# sheet1.net
KiCad netlist of a schematic drawn in Altium Designer
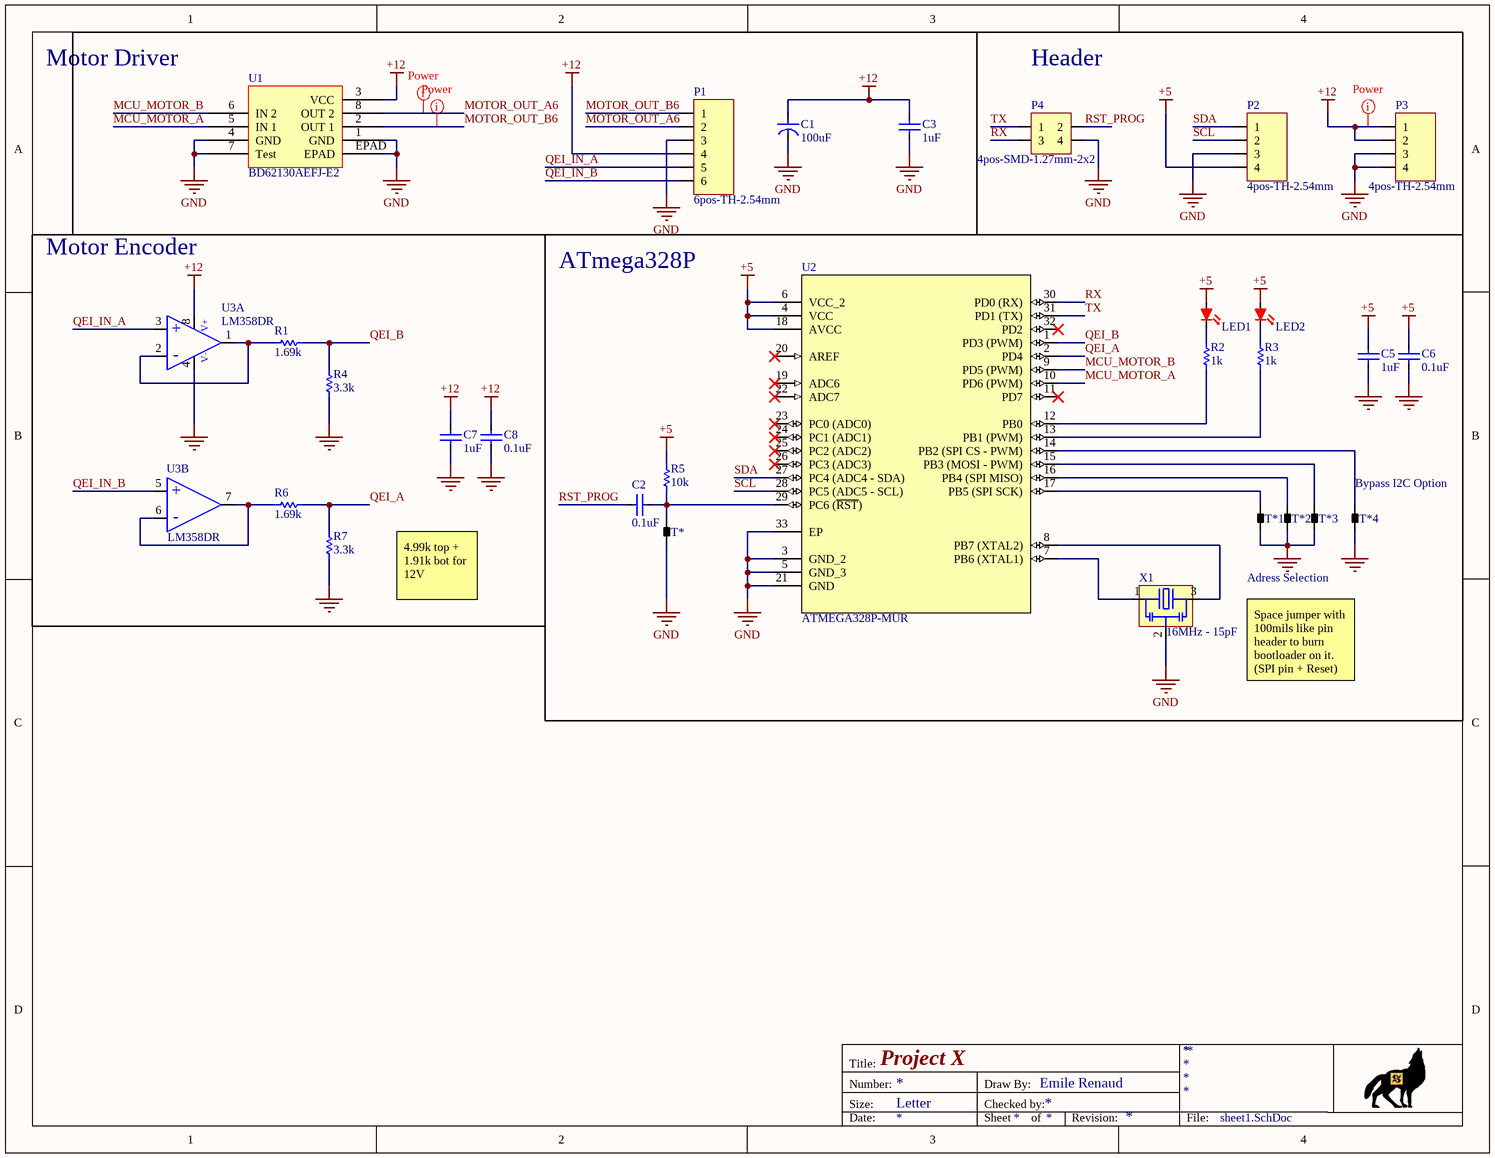
[diagram p0: sheet1.SchDoc]

(export (version "E")
  (design (tool "Eeschema 10.0.6"))
  (components
    (comp (ref "C1")
      (value "100uF")
      (footprint "CAPACITOR-Aluminium-5x11mm-2mmPitch")
      (description "CAP ALUM 100UF 20% 25V RADIAL")
      (libsource (lib "Capacitors-Electrolytic") (part "Capacitor-100uF-25V"))
    )
    (comp (ref "C2")
      (value "0.1uF")
      (footprint "CAPACITOR-0603")
      (description "Capacitor-0603-0.1uF-50V-X7R")
      (libsource (lib "Capacitors") (part "Capacitor-0603-0.1uF-50V-X7R"))
    )
    (comp (ref "C3")
      (value "1uF")
      (footprint "CAPACITOR-0603")
      (description "Capacitor-0603-1uF-25V-X5R")
      (libsource (lib "Capacitors") (part "Capacitor-0603-1uF-25V-X5R"))
    )
    (comp (ref "C5")
      (value "1uF")
      (footprint "CAPACITOR-0603")
      (description "Capacitor-0603-1uF-25V-X5R")
      (libsource (lib "Capacitors") (part "Capacitor-0603-1uF-25V-X5R"))
    )
    (comp (ref "C6")
      (value "0.1uF")
      (footprint "CAPACITOR-0603")
      (description "Capacitor-0603-0.1uF-50V-X7R")
      (libsource (lib "Capacitors") (part "Capacitor-0603-0.1uF-50V-X7R"))
    )
    (comp (ref "C7")
      (value "1uF")
      (footprint "CAPACITOR-0603")
      (description "Capacitor-0603-1uF-25V-X5R")
      (libsource (lib "Capacitors") (part "Capacitor-0603-1uF-25V-X5R"))
    )
    (comp (ref "C8")
      (value "0.1uF")
      (footprint "CAPACITOR-0603")
      (description "Capacitor-0603-0.1uF-50V-X7R")
      (libsource (lib "Capacitors") (part "Capacitor-0603-0.1uF-50V-X7R"))
    )
    (comp (ref "LED1")
      (value "B1911USD-20D000114U1930")
      (footprint "LED-0603-2PIN")
      (description "LED RED CLEAR 1608 SMD")
      (libsource (lib "LEDs") (part "B1911USD-20D000114U1930"))
    )
    (comp (ref "LED2")
      (value "B1911USD-20D000114U1930")
      (footprint "LED-0603-2PIN")
      (description "LED RED CLEAR 1608 SMD")
      (libsource (lib "LEDs") (part "B1911USD-20D000114U1930"))
    )
    (comp (ref "P1")
      (value "6pos-TH-2.54mm")
      (footprint "HDR1X6")
      (description "6pos TH 2.54mm Header")
      (libsource (lib "Header") (part "6pos-TH-2.54mm"))
    )
    (comp (ref "P2")
      (value "4pos-TH-2.54mm")
      (footprint "HDR1X4")
      (description "4pos TH 2.54mm Header")
      (libsource (lib "Header") (part "4pos-TH-2.54mm"))
    )
    (comp (ref "P3")
      (value "4pos-TH-2.54mm")
      (footprint "HDR1X4")
      (description "4pos TH 2.54mm Header")
      (libsource (lib "Header") (part "4pos-TH-2.54mm"))
    )
    (comp (ref "P4")
      (value "4pos-SMD-1.27mm-2x2")
      (footprint "PCB_Footprints:HDR2X2-SMD-50mils")
      (description "4pos SMD 1.27mm")
      (libsource (lib "Header") (part "4pos-SMD-1.27mm-2x2"))
    )
    (comp (ref "R1")
      (value "1.69k")
      (footprint "Resistor-0603")
      (description "Resistor0603-1.69k")
      (fields (field (name "Comment") "SMT resistor"))
      (libsource (lib "Resistors") (part "Resistor0603-1.69k"))
    )
    (comp (ref "R2")
      (value "1k")
      (footprint "Resistor-0603")
      (description "Resistor0603-1k")
      (fields (field (name "Comment") "SMT resistor"))
      (libsource (lib "Resistors") (part "Resistor0603-1k"))
    )
    (comp (ref "R3")
      (value "1k")
      (footprint "Resistor-0603")
      (description "Resistor0603-1k")
      (fields (field (name "Comment") "SMT resistor"))
      (libsource (lib "Resistors") (part "Resistor0603-1k"))
    )
    (comp (ref "R4")
      (value "3.3k")
      (footprint "Resistor-0603")
      (description "Resistor0603-3.3k")
      (fields (field (name "Comment") "SMT resistor"))
      (libsource (lib "Resistors") (part "Resistor0603-3.3k"))
    )
    (comp (ref "R5")
      (value "10k")
      (footprint "Resistor-0603")
      (description "Resistor0603-10k")
      (fields (field (name "Comment") "SMT resistor"))
      (libsource (lib "Resistors") (part "Resistor0603-10k"))
    )
    (comp (ref "R6")
      (value "1.69k")
      (footprint "Resistor-0603")
      (description "Resistor0603-1.69k")
      (fields (field (name "Comment") "SMT resistor"))
      (libsource (lib "Resistors") (part "Resistor0603-1.69k"))
    )
    (comp (ref "R7")
      (value "3.3k")
      (footprint "Resistor-0603")
      (description "Resistor0603-3.3k")
      (fields (field (name "Comment") "SMT resistor"))
      (libsource (lib "Resistors") (part "Resistor0603-3.3k"))
    )
    (comp (ref "T*")
      (value "NetTie_0603_Short")
      (footprint "NetTie-0603-short")
      (libsource (lib "JumpersAndHoles") (part "NetTie_0603_Short"))
    )
    (comp (ref "T*1")
      (value "NetTie_0603_Short")
      (footprint "NetTie-0603-short")
      (libsource (lib "JumpersAndHoles") (part "NetTie_0603_Short"))
    )
    (comp (ref "T*2")
      (value "NetTie_0603_Short")
      (footprint "NetTie-0603-short")
      (libsource (lib "JumpersAndHoles") (part "NetTie_0603_Short"))
    )
    (comp (ref "T*3")
      (value "NetTie_0603_Short")
      (footprint "NetTie-0603-short")
      (libsource (lib "JumpersAndHoles") (part "NetTie_0603_Short"))
    )
    (comp (ref "T*4")
      (value "NetTie_0603_Short")
      (footprint "NetTie-0603-short")
      (libsource (lib "JumpersAndHoles") (part "NetTie_0603_Short"))
    )
    (comp (ref "U1")
      (value "BD62130AEFJ-E2")
      (footprint "P-HSOP8")
      (description "1 CHANNEL H BRIDGE Motor. 28V, 3A")
      (libsource (lib "MotorDrivers") (part "BD62130AEFJ-E2"))
    )
    (comp (ref "U2")
      (value "ATMEGA328P-MUR")
      (footprint "VFQFN-32 Exposed Pad")
      (description "AVR AVR® ATmega Microcontroller IC 8-Bit 20MHz 32KB (16K x 16) FLASH 32-VQFN (5x5)")
      (libsource (lib "Microcontrollers") (part "ATMEGA328P-MUR"))
    )
    (comp (ref "U3")
      (value "LM358DR")
      (footprint "SOIC-8")
      (description "IC OPAMP GP 2 CIRCUIT 8SOIC")
      (libsource (lib "OperationalAmplifiers") (part "LM358DR"))
    )
    (comp (ref "X1")
      (value "16MHz - 15pF")
      (footprint "Resonator-CSTNE")
      (description "CERAMIC RES 16.0000MHZ 15PF SMD")
      (fields (field (name "Comment") "CSTNE16M0V530000R0"))
      (libsource (lib "Crystals") (part "CSTNE16M0V530000R0"))
    )
  )
  (nets
    (net (code "1") (name "+5") (class "Default")
      (node (ref "C5") (pin "2") (pinfunction "2_2") (pintype "passive"))
      (node (ref "C6") (pin "2") (pinfunction "2_2") (pintype "passive"))
      (node (ref "LED1") (pin "2") (pinfunction "R_2") (pintype "passive"))
      (node (ref "LED2") (pin "2") (pinfunction "R_2") (pintype "passive"))
      (node (ref "P2") (pin "4") (pinfunction "4_4") (pintype "passive"))
      (node (ref "R5") (pin "2") (pinfunction "2_2") (pintype "passive"))
      (node (ref "U2") (pin "18") (pinfunction "AVCC_18") (pintype "power_in"))
      (node (ref "U2") (pin "4") (pinfunction "VCC_4") (pintype "power_in"))
      (node (ref "U2") (pin "6") (pinfunction "VCC_2_6") (pintype "power_in"))
    )
    (net (code "2") (name "+12") (class "Default")
      (node (ref "C1") (pin "1") (pinfunction "1_1") (pintype "passive"))
      (node (ref "C3") (pin "2") (pinfunction "2_2") (pintype "passive"))
      (node (ref "C7") (pin "2") (pinfunction "2_2") (pintype "passive"))
      (node (ref "C8") (pin "2") (pinfunction "2_2") (pintype "passive"))
      (node (ref "P1") (pin "4") (pinfunction "4_4") (pintype "passive"))
      (node (ref "P3") (pin "1") (pinfunction "1_1") (pintype "passive"))
      (node (ref "P3") (pin "2") (pinfunction "2_2") (pintype "passive"))
      (node (ref "U1") (pin "3") (pinfunction "VCC_3") (pintype "passive"))
      (node (ref "U3") (pin "8") (pinfunction "VS+_8") (pintype "passive"))
    )
    (net (code "3") (name "/MCU_MOTOR_A") (class "Default")
      (node (ref "U1") (pin "5") (pinfunction "IN_1_5") (pintype "passive"))
      (node (ref "U2") (pin "10") (pinfunction "PD6_(PWM)_10") (pintype "bidirectional"))
    )
    (net (code "4") (name "/MCU_MOTOR_B") (class "Default")
      (node (ref "U1") (pin "6") (pinfunction "IN_2_6") (pintype "passive"))
      (node (ref "U2") (pin "9") (pinfunction "PD5_(PWM)_9") (pintype "bidirectional"))
    )
    (net (code "5") (name "/MOTOR_OUT_A6") (class "Default")
      (node (ref "P1") (pin "2") (pinfunction "2_2") (pintype "passive"))
      (node (ref "U1") (pin "8") (pinfunction "OUT_2_8") (pintype "passive"))
    )
    (net (code "6") (name "/MOTOR_OUT_B6") (class "Default")
      (node (ref "P1") (pin "1") (pinfunction "1_1") (pintype "passive"))
      (node (ref "U1") (pin "2") (pinfunction "OUT_1_2") (pintype "passive"))
    )
    (net (code "7") (name "/QEI_A") (class "Default")
      (node (ref "R6") (pin "2") (pinfunction "2_2") (pintype "passive"))
      (node (ref "R7") (pin "2") (pinfunction "2_2") (pintype "passive"))
      (node (ref "U2") (pin "2") (pinfunction "PD4_2") (pintype "bidirectional"))
    )
    (net (code "8") (name "/QEI_B") (class "Default")
      (node (ref "R1") (pin "2") (pinfunction "2_2") (pintype "passive"))
      (node (ref "R4") (pin "2") (pinfunction "2_2") (pintype "passive"))
      (node (ref "U2") (pin "1") (pinfunction "PD3_(PWM)_1") (pintype "bidirectional"))
    )
    (net (code "9") (name "/QEI_IN_A") (class "Default")
      (node (ref "P1") (pin "5") (pinfunction "5_5") (pintype "passive"))
      (node (ref "U3") (pin "3") (pinfunction "IN1+_3") (pintype "passive"))
    )
    (net (code "10") (name "/QEI_IN_B") (class "Default")
      (node (ref "P1") (pin "6") (pinfunction "6_6") (pintype "passive"))
      (node (ref "U3") (pin "5") (pinfunction "IN2+_5") (pintype "passive"))
    )
    (net (code "11") (name "/RST_PROG") (class "Default")
      (node (ref "C2") (pin "1") (pinfunction "1_1") (pintype "passive"))
      (node (ref "P4") (pin "2") (pinfunction "2_2") (pintype "passive"))
    )
    (net (code "12") (name "/RX") (class "Default")
      (node (ref "P4") (pin "3") (pinfunction "3_3") (pintype "passive"))
      (node (ref "U2") (pin "30") (pinfunction "PD0_(RX)_30") (pintype "bidirectional"))
    )
    (net (code "13") (name "/SCL") (class "Default")
      (node (ref "P2") (pin "2") (pinfunction "2_2") (pintype "passive"))
      (node (ref "U2") (pin "28") (pinfunction "PC5_(ADC5_-_SCL)_28") (pintype "bidirectional"))
    )
    (net (code "14") (name "/SDA") (class "Default")
      (node (ref "P2") (pin "1") (pinfunction "1_1") (pintype "passive"))
      (node (ref "U2") (pin "27") (pinfunction "PC4_(ADC4_-_SDA)_27") (pintype "bidirectional"))
    )
    (net (code "15") (name "/TX") (class "Default")
      (node (ref "P4") (pin "1") (pinfunction "1_1") (pintype "passive"))
      (node (ref "U2") (pin "31") (pinfunction "PD1_(TX)_31") (pintype "bidirectional"))
    )
    (net (code "16") (name "GND") (class "Default")
      (node (ref "C1") (pin "2") (pinfunction "2_2") (pintype "passive"))
      (node (ref "C3") (pin "1") (pinfunction "1_1") (pintype "passive"))
      (node (ref "C5") (pin "1") (pinfunction "1_1") (pintype "passive"))
      (node (ref "C6") (pin "1") (pinfunction "1_1") (pintype "passive"))
      (node (ref "C7") (pin "1") (pinfunction "1_1") (pintype "passive"))
      (node (ref "C8") (pin "1") (pinfunction "1_1") (pintype "passive"))
      (node (ref "P1") (pin "3") (pinfunction "3_3") (pintype "passive"))
      (node (ref "P2") (pin "3") (pinfunction "3_3") (pintype "passive"))
      (node (ref "P3") (pin "3") (pinfunction "3_3") (pintype "passive"))
      (node (ref "P3") (pin "4") (pinfunction "4_4") (pintype "passive"))
      (node (ref "P4") (pin "4") (pinfunction "4_4") (pintype "passive"))
      (node (ref "R4") (pin "1") (pinfunction "1_1") (pintype "passive"))
      (node (ref "R7") (pin "1") (pinfunction "1_1") (pintype "passive"))
      (node (ref "T*") (pin "2") (pinfunction "2_2") (pintype "passive"))
      (node (ref "T*1") (pin "2") (pinfunction "2_2") (pintype "passive"))
      (node (ref "T*2") (pin "2") (pinfunction "2_2") (pintype "passive"))
      (node (ref "T*3") (pin "2") (pinfunction "2_2") (pintype "passive"))
      (node (ref "T*4") (pin "2") (pinfunction "2_2") (pintype "passive"))
      (node (ref "U1") (pin "1") (pinfunction "GND_1") (pintype "passive"))
      (node (ref "U1") (pin "4") (pinfunction "GND_4") (pintype "passive"))
      (node (ref "U1") (pin "7") (pinfunction "Test_7") (pintype "passive"))
      (node (ref "U1") (pin "EPAD") (pinfunction "EPAD_EPAD") (pintype "passive"))
      (node (ref "U2") (pin "21") (pinfunction "GND_21") (pintype "passive"))
      (node (ref "U2") (pin "3") (pinfunction "GND_2_3") (pintype "passive"))
      (node (ref "U2") (pin "33") (pinfunction "EP_33") (pintype "passive"))
      (node (ref "U2") (pin "5") (pinfunction "GND_3_5") (pintype "passive"))
      (node (ref "U3") (pin "4") (pinfunction "VS-_4") (pintype "passive"))
      (node (ref "X1") (pin "2") (pintype "passive"))
    )
    (net (code "17") (name "Net-(LED1-K)") (class "Default")
      (node (ref "LED1") (pin "1") (pinfunction "K_1") (pintype "passive"))
      (node (ref "R2") (pin "2") (pinfunction "2_2") (pintype "passive"))
    )
    (net (code "18") (name "Net-(LED2-K)") (class "Default")
      (node (ref "LED2") (pin "1") (pinfunction "K_1") (pintype "passive"))
      (node (ref "R3") (pin "2") (pinfunction "2_2") (pintype "passive"))
    )
    (net (code "19") (name "Net-(U2-PB0)") (class "Default")
      (node (ref "R2") (pin "1") (pinfunction "1_1") (pintype "passive"))
      (node (ref "U2") (pin "12") (pinfunction "PB0_12") (pintype "bidirectional"))
    )
    (net (code "20") (name "Net-(U2-PB1_(PWM))") (class "Default")
      (node (ref "R3") (pin "1") (pinfunction "1_1") (pintype "passive"))
      (node (ref "U2") (pin "13") (pinfunction "PB1_(PWM)_13") (pintype "bidirectional"))
    )
    (net (code "21") (name "Net-(U2-PB2_(SPI_CS_-_PWM))") (class "Default")
      (node (ref "T*4") (pin "1") (pinfunction "1_1") (pintype "passive"))
      (node (ref "U2") (pin "14") (pinfunction "PB2_(SPI_CS_-_PWM)_14") (pintype "bidirectional"))
    )
    (net (code "22") (name "Net-(U2-PB3_(MOSI_-_PWM))") (class "Default")
      (node (ref "T*3") (pin "1") (pinfunction "1_1") (pintype "passive"))
      (node (ref "U2") (pin "15") (pinfunction "PB3_(MOSI_-_PWM)_15") (pintype "bidirectional"))
    )
    (net (code "23") (name "Net-(U2-PB4_(SPI_MISO))") (class "Default")
      (node (ref "T*2") (pin "1") (pinfunction "1_1") (pintype "passive"))
      (node (ref "U2") (pin "16") (pinfunction "PB4_(SPI_MISO)_16") (pintype "bidirectional"))
    )
    (net (code "24") (name "Net-(U2-PB5_(SPI_SCK))") (class "Default")
      (node (ref "T*1") (pin "1") (pinfunction "1_1") (pintype "passive"))
      (node (ref "U2") (pin "17") (pinfunction "PB5_(SPI_SCK)_17") (pintype "bidirectional"))
    )
    (net (code "25") (name "Net-(U2-PB6_(XTAL1))") (class "Default")
      (node (ref "U2") (pin "7") (pinfunction "PB6_(XTAL1)_7") (pintype "bidirectional"))
      (node (ref "X1") (pin "1") (pintype "passive"))
    )
    (net (code "26") (name "Net-(U2-PB7_(XTAL2))") (class "Default")
      (node (ref "U2") (pin "8") (pinfunction "PB7_(XTAL2)_8") (pintype "bidirectional"))
      (node (ref "X1") (pin "3") (pintype "passive"))
    )
    (net (code "27") (name "Net-(U2-PC6_(~{RST}))") (class "Default")
      (node (ref "C2") (pin "2") (pinfunction "2_2") (pintype "passive"))
      (node (ref "R5") (pin "1") (pinfunction "1_1") (pintype "passive"))
      (node (ref "T*") (pin "1") (pinfunction "1_1") (pintype "passive"))
      (node (ref "U2") (pin "29") (pinfunction "PC6_(~{RST})_29") (pintype "bidirectional"))
    )
    (net (code "28") (name "Net-(U3A-IN1-)") (class "Default")
      (node (ref "R1") (pin "1") (pinfunction "1_1") (pintype "passive"))
      (node (ref "U3") (pin "1") (pinfunction "OUT1_1") (pintype "passive"))
      (node (ref "U3") (pin "2") (pinfunction "IN1-_2") (pintype "passive"))
    )
    (net (code "29") (name "Net-(U3B-IN2-)") (class "Default")
      (node (ref "R6") (pin "1") (pinfunction "1_1") (pintype "passive"))
      (node (ref "U3") (pin "6") (pinfunction "IN2-_6") (pintype "passive"))
      (node (ref "U3") (pin "7") (pinfunction "OUT_7") (pintype "passive"))
    )
    (net (code "30") (name "unconnected-(U2-ADC6-Pad19)") (class "Default")
      (node (ref "U2") (pin "19") (pinfunction "ADC6_19") (pintype "input+no_connect"))
    )
    (net (code "31") (name "unconnected-(U2-ADC7-Pad22)") (class "Default")
      (node (ref "U2") (pin "22") (pinfunction "ADC7_22") (pintype "input+no_connect"))
    )
    (net (code "32") (name "unconnected-(U2-AREF-Pad20)") (class "Default")
      (node (ref "U2") (pin "20") (pinfunction "AREF_20") (pintype "input+no_connect"))
    )
    (net (code "33") (name "unconnected-(U2-PC0_(ADC0)-Pad23)") (class "Default")
      (node (ref "U2") (pin "23") (pinfunction "PC0_(ADC0)_23") (pintype "bidirectional+no_connect"))
    )
    (net (code "34") (name "unconnected-(U2-PC1_(ADC1)-Pad24)") (class "Default")
      (node (ref "U2") (pin "24") (pinfunction "PC1_(ADC1)_24") (pintype "bidirectional+no_connect"))
    )
    (net (code "35") (name "unconnected-(U2-PC2_(ADC2)-Pad25)") (class "Default")
      (node (ref "U2") (pin "25") (pinfunction "PC2_(ADC2)_25") (pintype "bidirectional+no_connect"))
    )
    (net (code "36") (name "unconnected-(U2-PC3_(ADC3)-Pad26)") (class "Default")
      (node (ref "U2") (pin "26") (pinfunction "PC3_(ADC3)_26") (pintype "bidirectional+no_connect"))
    )
    (net (code "37") (name "unconnected-(U2-PD2-Pad32)") (class "Default")
      (node (ref "U2") (pin "32") (pinfunction "PD2_32") (pintype "bidirectional+no_connect"))
    )
    (net (code "38") (name "unconnected-(U2-PD7-Pad11)") (class "Default")
      (node (ref "U2") (pin "11") (pinfunction "PD7_11") (pintype "bidirectional+no_connect"))
    )
  )
)
